# main.net
KiCad netlist of a schematic drawn in EAGLE
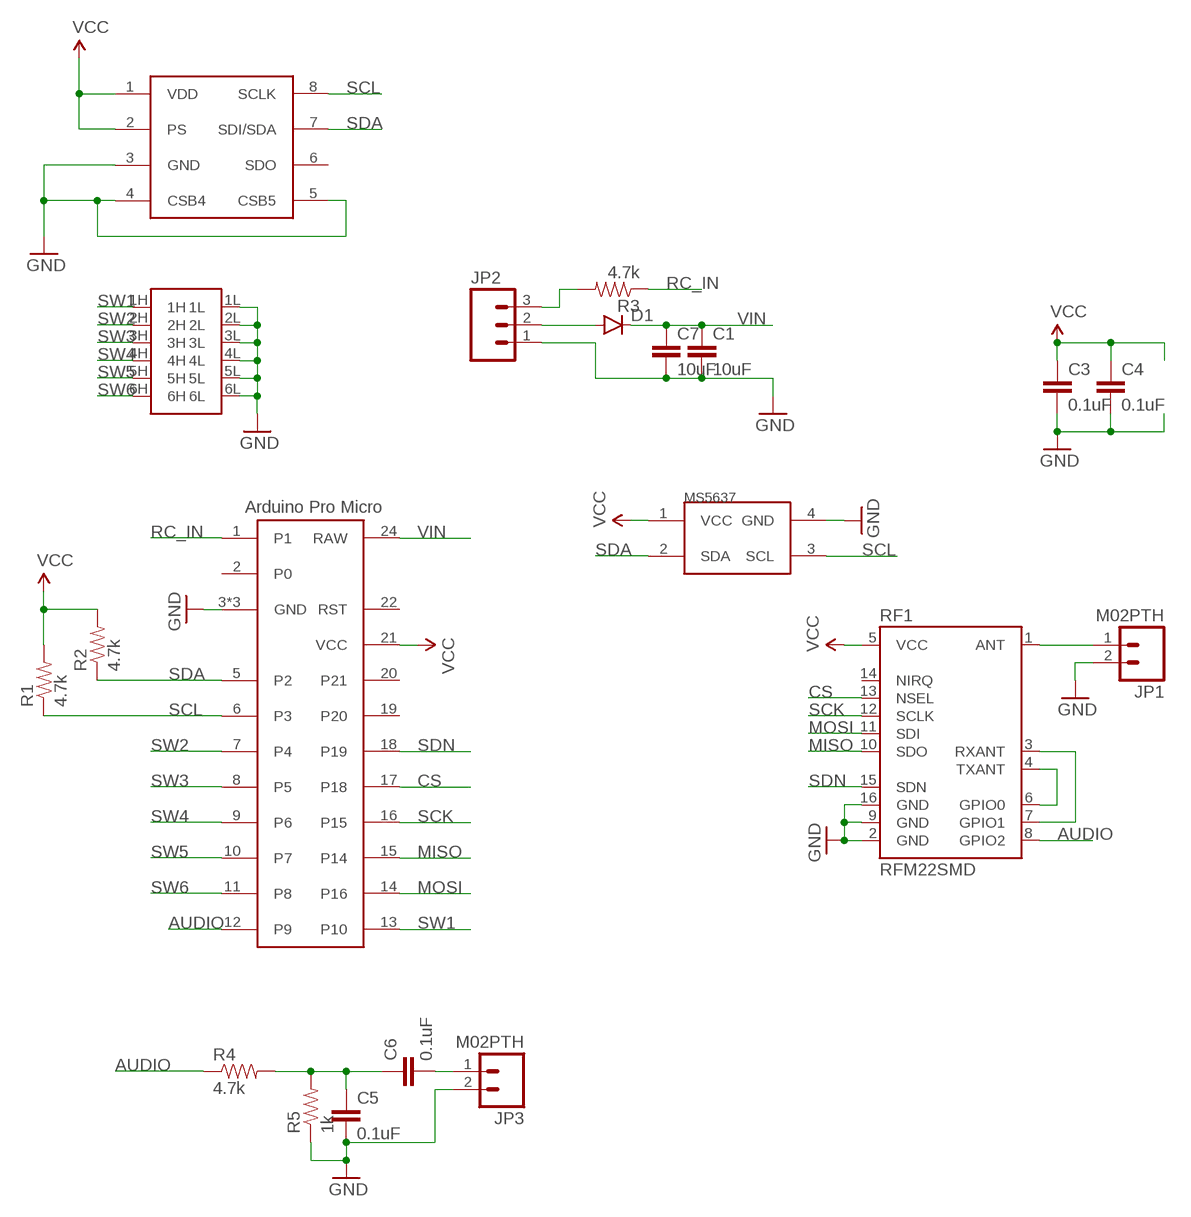
[diagram p0: schematic, sheet 1]

(export (version "E")
  (design (tool "Eeschema 10.0.6"))
  (components
    (comp (ref "C1")
      (value "10uF")
      (footprint "eagle-import:0805")
      (libsource (lib "eagle-import") (part "CAP0805"))
    )
    (comp (ref "C3")
      (value "0.1uF")
      (footprint "eagle-import:0603-CAP")
      (libsource (lib "eagle-import") (part "CAP0603-CAP"))
    )
    (comp (ref "C4")
      (value "0.1uF")
      (footprint "eagle-import:0603-CAP")
      (libsource (lib "eagle-import") (part "CAP0603-CAP"))
    )
    (comp (ref "C5")
      (value "0.1uF")
      (footprint "eagle-import:0603-CAP")
      (libsource (lib "eagle-import") (part "CAP0603-CAP"))
    )
    (comp (ref "C6")
      (value "0.1uF")
      (footprint "eagle-import:0603-CAP")
      (libsource (lib "eagle-import") (part "CAP0603-CAP"))
    )
    (comp (ref "C7")
      (value "10uF")
      (footprint "eagle-import:0805")
      (libsource (lib "eagle-import") (part "CAP0805"))
    )
    (comp (ref "D1")
      (value "DIODESMA")
      (footprint "eagle-import:SMA-DIODE")
      (libsource (lib "eagle-import") (part "DIODESMA"))
    )
    (comp (ref "JP1")
      (value "M02PTH")
      (footprint "eagle-import:1X02")
      (libsource (lib "eagle-import") (part "M02PTH"))
    )
    (comp (ref "JP2")
      (value "M03PTH")
      (footprint "eagle-import:1X03")
      (libsource (lib "eagle-import") (part "M03PTH"))
    )
    (comp (ref "JP3")
      (value "M02PTH")
      (footprint "eagle-import:1X02")
      (libsource (lib "eagle-import") (part "M02PTH"))
    )
    (comp (ref "R1")
      (value "4.7k")
      (footprint "eagle-import:0603-RES")
      (libsource (lib "eagle-import") (part "RESISTOR0603-RES"))
    )
    (comp (ref "R2")
      (value "4.7k")
      (footprint "eagle-import:0603-RES")
      (libsource (lib "eagle-import") (part "RESISTOR0603-RES"))
    )
    (comp (ref "R3")
      (value "4.7k")
      (footprint "eagle-import:0603-RES")
      (libsource (lib "eagle-import") (part "RESISTOR0603-RES"))
    )
    (comp (ref "R4")
      (value "4.7k")
      (footprint "eagle-import:0603-RES")
      (libsource (lib "eagle-import") (part "RESISTOR0603-RES"))
    )
    (comp (ref "R5")
      (value "1k")
      (footprint "eagle-import:0603-RES")
      (libsource (lib "eagle-import") (part "RESISTOR0603-RES"))
    )
    (comp (ref "RF1")
      (value "RFM22SMD")
      (footprint "eagle-import:RFM22-XXX-S2")
      (libsource (lib "eagle-import") (part "RFM22SMD"))
    )
    (comp (ref "U$1")
      (value "PRO_MICRO")
      (footprint "eagle-import:PRO_MICRO")
      (libsource (lib "eagle-import") (part "PRO_MICRO"))
    )
    (comp (ref "U$2")
      (value "DIPSWITCH6")
      (footprint "eagle-import:DIPSWITCH6")
      (libsource (lib "eagle-import") (part "DIPSWITCH6"))
    )
    (comp (ref "U$3")
      (value "MS5637")
      (footprint "eagle-import:MS5637")
      (libsource (lib "eagle-import") (part "MS5637"))
    )
    (comp (ref "U$4")
      (value "MS5611")
      (footprint "eagle-import:MS5611")
      (libsource (lib "eagle-import") (part "MS5611"))
    )
  )
  (nets
    (net (code "1") (name "/AUDIO") (class "Default")
      (node (ref "R4") (pin "1") (pinfunction "1_1") (pintype "passive"))
      (node (ref "RF1") (pin "8") (pinfunction "GPIO2_8") (pintype "bidirectional"))
      (node (ref "U$1") (pin "12") (pinfunction "P9_12") (pintype "bidirectional"))
    )
    (net (code "2") (name "/CS") (class "Default")
      (node (ref "RF1") (pin "13") (pinfunction "NSEL_13") (pintype "input"))
      (node (ref "U$1") (pin "17") (pinfunction "P18_17") (pintype "bidirectional"))
    )
    (net (code "3") (name "/MISO") (class "Default")
      (node (ref "RF1") (pin "10") (pinfunction "SDO_10") (pintype "output"))
      (node (ref "U$1") (pin "15") (pinfunction "P14_15") (pintype "bidirectional"))
    )
    (net (code "4") (name "/MOSI") (class "Default")
      (node (ref "RF1") (pin "11") (pinfunction "SDI_11") (pintype "input"))
      (node (ref "U$1") (pin "14") (pinfunction "P16_14") (pintype "bidirectional"))
    )
    (net (code "5") (name "/RC_IN") (class "Default")
      (node (ref "R3") (pin "1") (pinfunction "1_1") (pintype "passive"))
      (node (ref "U$1") (pin "1") (pinfunction "P1_1") (pintype "bidirectional"))
    )
    (net (code "6") (name "/SCK") (class "Default")
      (node (ref "RF1") (pin "12") (pinfunction "SCLK_12") (pintype "input"))
      (node (ref "U$1") (pin "16") (pinfunction "P15_16") (pintype "bidirectional"))
    )
    (net (code "7") (name "/SCL") (class "Default")
      (node (ref "R1") (pin "1") (pinfunction "1_1") (pintype "passive"))
      (node (ref "U$1") (pin "6") (pinfunction "P3_6") (pintype "bidirectional"))
      (node (ref "U$3") (pin "3") (pinfunction "SCL_3") (pintype "bidirectional"))
      (node (ref "U$4") (pin "8") (pinfunction "SCLK_8") (pintype "bidirectional"))
    )
    (net (code "8") (name "/SDA") (class "Default")
      (node (ref "R2") (pin "1") (pinfunction "1_1") (pintype "passive"))
      (node (ref "U$1") (pin "5") (pinfunction "P2_5") (pintype "bidirectional"))
      (node (ref "U$3") (pin "2") (pinfunction "SDA_2") (pintype "bidirectional"))
      (node (ref "U$4") (pin "7") (pinfunction "SDI/SDA_7") (pintype "bidirectional"))
    )
    (net (code "9") (name "/SDN") (class "Default")
      (node (ref "RF1") (pin "15") (pinfunction "SDN_15") (pintype "input"))
      (node (ref "U$1") (pin "18") (pinfunction "P19_18") (pintype "bidirectional"))
    )
    (net (code "10") (name "/SW1") (class "Default")
      (node (ref "U$1") (pin "13") (pinfunction "P10_13") (pintype "bidirectional"))
      (node (ref "U$2") (pin "1H") (pinfunction "1H_1H") (pintype "bidirectional"))
    )
    (net (code "11") (name "/SW2") (class "Default")
      (node (ref "U$1") (pin "7") (pinfunction "P4_7") (pintype "bidirectional"))
      (node (ref "U$2") (pin "2H") (pinfunction "2H_2H") (pintype "bidirectional"))
    )
    (net (code "12") (name "/SW3") (class "Default")
      (node (ref "U$1") (pin "8") (pinfunction "P5_8") (pintype "bidirectional"))
      (node (ref "U$2") (pin "3H") (pinfunction "3H_3H") (pintype "bidirectional"))
    )
    (net (code "13") (name "/SW4") (class "Default")
      (node (ref "U$1") (pin "9") (pinfunction "P6_9") (pintype "bidirectional"))
      (node (ref "U$2") (pin "4H") (pinfunction "4H_4H") (pintype "bidirectional"))
    )
    (net (code "14") (name "/SW5") (class "Default")
      (node (ref "U$1") (pin "10") (pinfunction "P7_10") (pintype "bidirectional"))
      (node (ref "U$2") (pin "5H") (pinfunction "5H_5H") (pintype "bidirectional"))
    )
    (net (code "15") (name "/SW6") (class "Default")
      (node (ref "U$1") (pin "11") (pinfunction "P8_11") (pintype "bidirectional"))
      (node (ref "U$2") (pin "6H") (pinfunction "6H_6H") (pintype "bidirectional"))
    )
    (net (code "16") (name "/VIN") (class "Default")
      (node (ref "C1") (pin "1") (pinfunction "1_1") (pintype "passive"))
      (node (ref "C7") (pin "1") (pinfunction "1_1") (pintype "passive"))
      (node (ref "D1") (pin "C") (pinfunction "C_C") (pintype "passive"))
      (node (ref "U$1") (pin "24") (pinfunction "RAW_24") (pintype "bidirectional"))
    )
    (net (code "17") (name "GND") (class "Default")
      (node (ref "C1") (pin "2") (pinfunction "2_2") (pintype "passive"))
      (node (ref "C3") (pin "2") (pinfunction "2_2") (pintype "passive"))
      (node (ref "C4") (pin "2") (pinfunction "2_2") (pintype "passive"))
      (node (ref "C5") (pin "2") (pinfunction "2_2") (pintype "passive"))
      (node (ref "C7") (pin "2") (pinfunction "2_2") (pintype "passive"))
      (node (ref "JP1") (pin "2") (pinfunction "2_2") (pintype "passive"))
      (node (ref "JP2") (pin "1") (pinfunction "1_1") (pintype "passive"))
      (node (ref "JP3") (pin "2") (pinfunction "2_2") (pintype "passive"))
      (node (ref "R5") (pin "1") (pinfunction "1_1") (pintype "passive"))
      (node (ref "RF1") (pin "16") (pinfunction "GND_16") (pintype "power_in"))
      (node (ref "RF1") (pin "2") (pinfunction "GND_2") (pintype "power_in"))
      (node (ref "RF1") (pin "9") (pinfunction "GND_9") (pintype "power_in"))
      (node (ref "U$1") (pin "23") (pinfunction "GND_23") (pintype "bidirectional"))
      (node (ref "U$1") (pin "3") (pinfunction "GND_3") (pintype "bidirectional"))
      (node (ref "U$1") (pin "4") (pinfunction "GND_4") (pintype "bidirectional"))
      (node (ref "U$2") (pin "1L") (pinfunction "1L_1L") (pintype "bidirectional"))
      (node (ref "U$2") (pin "2L") (pinfunction "2L_2L") (pintype "bidirectional"))
      (node (ref "U$2") (pin "3L") (pinfunction "3L_3L") (pintype "bidirectional"))
      (node (ref "U$2") (pin "4L") (pinfunction "4L_4L") (pintype "bidirectional"))
      (node (ref "U$2") (pin "5L") (pinfunction "5L_5L") (pintype "bidirectional"))
      (node (ref "U$2") (pin "6L") (pinfunction "6L_6L") (pintype "bidirectional"))
      (node (ref "U$3") (pin "4") (pinfunction "GND_4") (pintype "bidirectional"))
      (node (ref "U$4") (pin "3") (pinfunction "GND_3") (pintype "bidirectional"))
      (node (ref "U$4") (pin "4") (pinfunction "CSB4_4") (pintype "bidirectional"))
      (node (ref "U$4") (pin "5") (pinfunction "CSB5_5") (pintype "bidirectional"))
    )
    (net (code "18") (name "Net-(C5-Pad1)") (class "Default")
      (node (ref "C5") (pin "1") (pinfunction "1_1") (pintype "passive"))
      (node (ref "C6") (pin "1") (pinfunction "1_1") (pintype "passive"))
      (node (ref "R4") (pin "2") (pinfunction "2_2") (pintype "passive"))
      (node (ref "R5") (pin "2") (pinfunction "2_2") (pintype "passive"))
    )
    (net (code "19") (name "Net-(C6-Pad2)") (class "Default")
      (node (ref "C6") (pin "2") (pinfunction "2_2") (pintype "passive"))
      (node (ref "JP3") (pin "1") (pinfunction "1_1") (pintype "passive"))
    )
    (net (code "20") (name "Net-(D1-PadA)") (class "Default")
      (node (ref "D1") (pin "A") (pinfunction "A_A") (pintype "passive"))
      (node (ref "JP2") (pin "2") (pinfunction "2_2") (pintype "passive"))
    )
    (net (code "21") (name "Net-(JP2-Pad3)") (class "Default")
      (node (ref "JP2") (pin "3") (pinfunction "3_3") (pintype "passive"))
      (node (ref "R3") (pin "2") (pinfunction "2_2") (pintype "passive"))
    )
    (net (code "22") (name "Net-(RF1-ANT)") (class "Default")
      (node (ref "JP1") (pin "1") (pinfunction "1_1") (pintype "passive"))
      (node (ref "RF1") (pin "1") (pinfunction "ANT_1") (pintype "bidirectional"))
    )
    (net (code "23") (name "Net-(RF1-GPIO0)") (class "Default")
      (node (ref "RF1") (pin "4") (pinfunction "TXANT_4") (pintype "input"))
      (node (ref "RF1") (pin "6") (pinfunction "GPIO0_6") (pintype "bidirectional"))
    )
    (net (code "24") (name "Net-(RF1-GPIO1)") (class "Default")
      (node (ref "RF1") (pin "3") (pinfunction "RXANT_3") (pintype "input"))
      (node (ref "RF1") (pin "7") (pinfunction "GPIO1_7") (pintype "bidirectional"))
    )
    (net (code "25") (name "VCC") (class "Default")
      (node (ref "C3") (pin "1") (pinfunction "1_1") (pintype "passive"))
      (node (ref "C4") (pin "1") (pinfunction "1_1") (pintype "passive"))
      (node (ref "R1") (pin "2") (pinfunction "2_2") (pintype "passive"))
      (node (ref "R2") (pin "2") (pinfunction "2_2") (pintype "passive"))
      (node (ref "RF1") (pin "5") (pinfunction "VCC_5") (pintype "bidirectional"))
      (node (ref "U$1") (pin "21") (pinfunction "VCC_21") (pintype "bidirectional"))
      (node (ref "U$3") (pin "1") (pinfunction "VCC_1") (pintype "bidirectional"))
      (node (ref "U$4") (pin "1") (pinfunction "VDD_1") (pintype "bidirectional"))
      (node (ref "U$4") (pin "2") (pinfunction "PS_2") (pintype "bidirectional"))
    )
    (net (code "26") (name "unconnected-(RF1-NIRQ-Pad14)") (class "Default")
      (node (ref "RF1") (pin "14") (pinfunction "NIRQ_14") (pintype "output"))
    )
    (net (code "27") (name "unconnected-(U$1-P0-Pad2)") (class "Default")
      (node (ref "U$1") (pin "2") (pinfunction "P0_2") (pintype "bidirectional"))
    )
    (net (code "28") (name "unconnected-(U$1-P20-Pad19)") (class "Default")
      (node (ref "U$1") (pin "19") (pinfunction "P20_19") (pintype "bidirectional"))
    )
    (net (code "29") (name "unconnected-(U$1-P21-Pad20)") (class "Default")
      (node (ref "U$1") (pin "20") (pinfunction "P21_20") (pintype "bidirectional"))
    )
    (net (code "30") (name "unconnected-(U$1-RST-Pad22)") (class "Default")
      (node (ref "U$1") (pin "22") (pinfunction "RST_22") (pintype "bidirectional"))
    )
    (net (code "31") (name "unconnected-(U$4-SDO-Pad6)") (class "Default")
      (node (ref "U$4") (pin "6") (pinfunction "SDO_6") (pintype "bidirectional"))
    )
  )
)
